# T11-MIDIThereminCPU.net
KiCad netlist of a schematic drawn in EAGLE
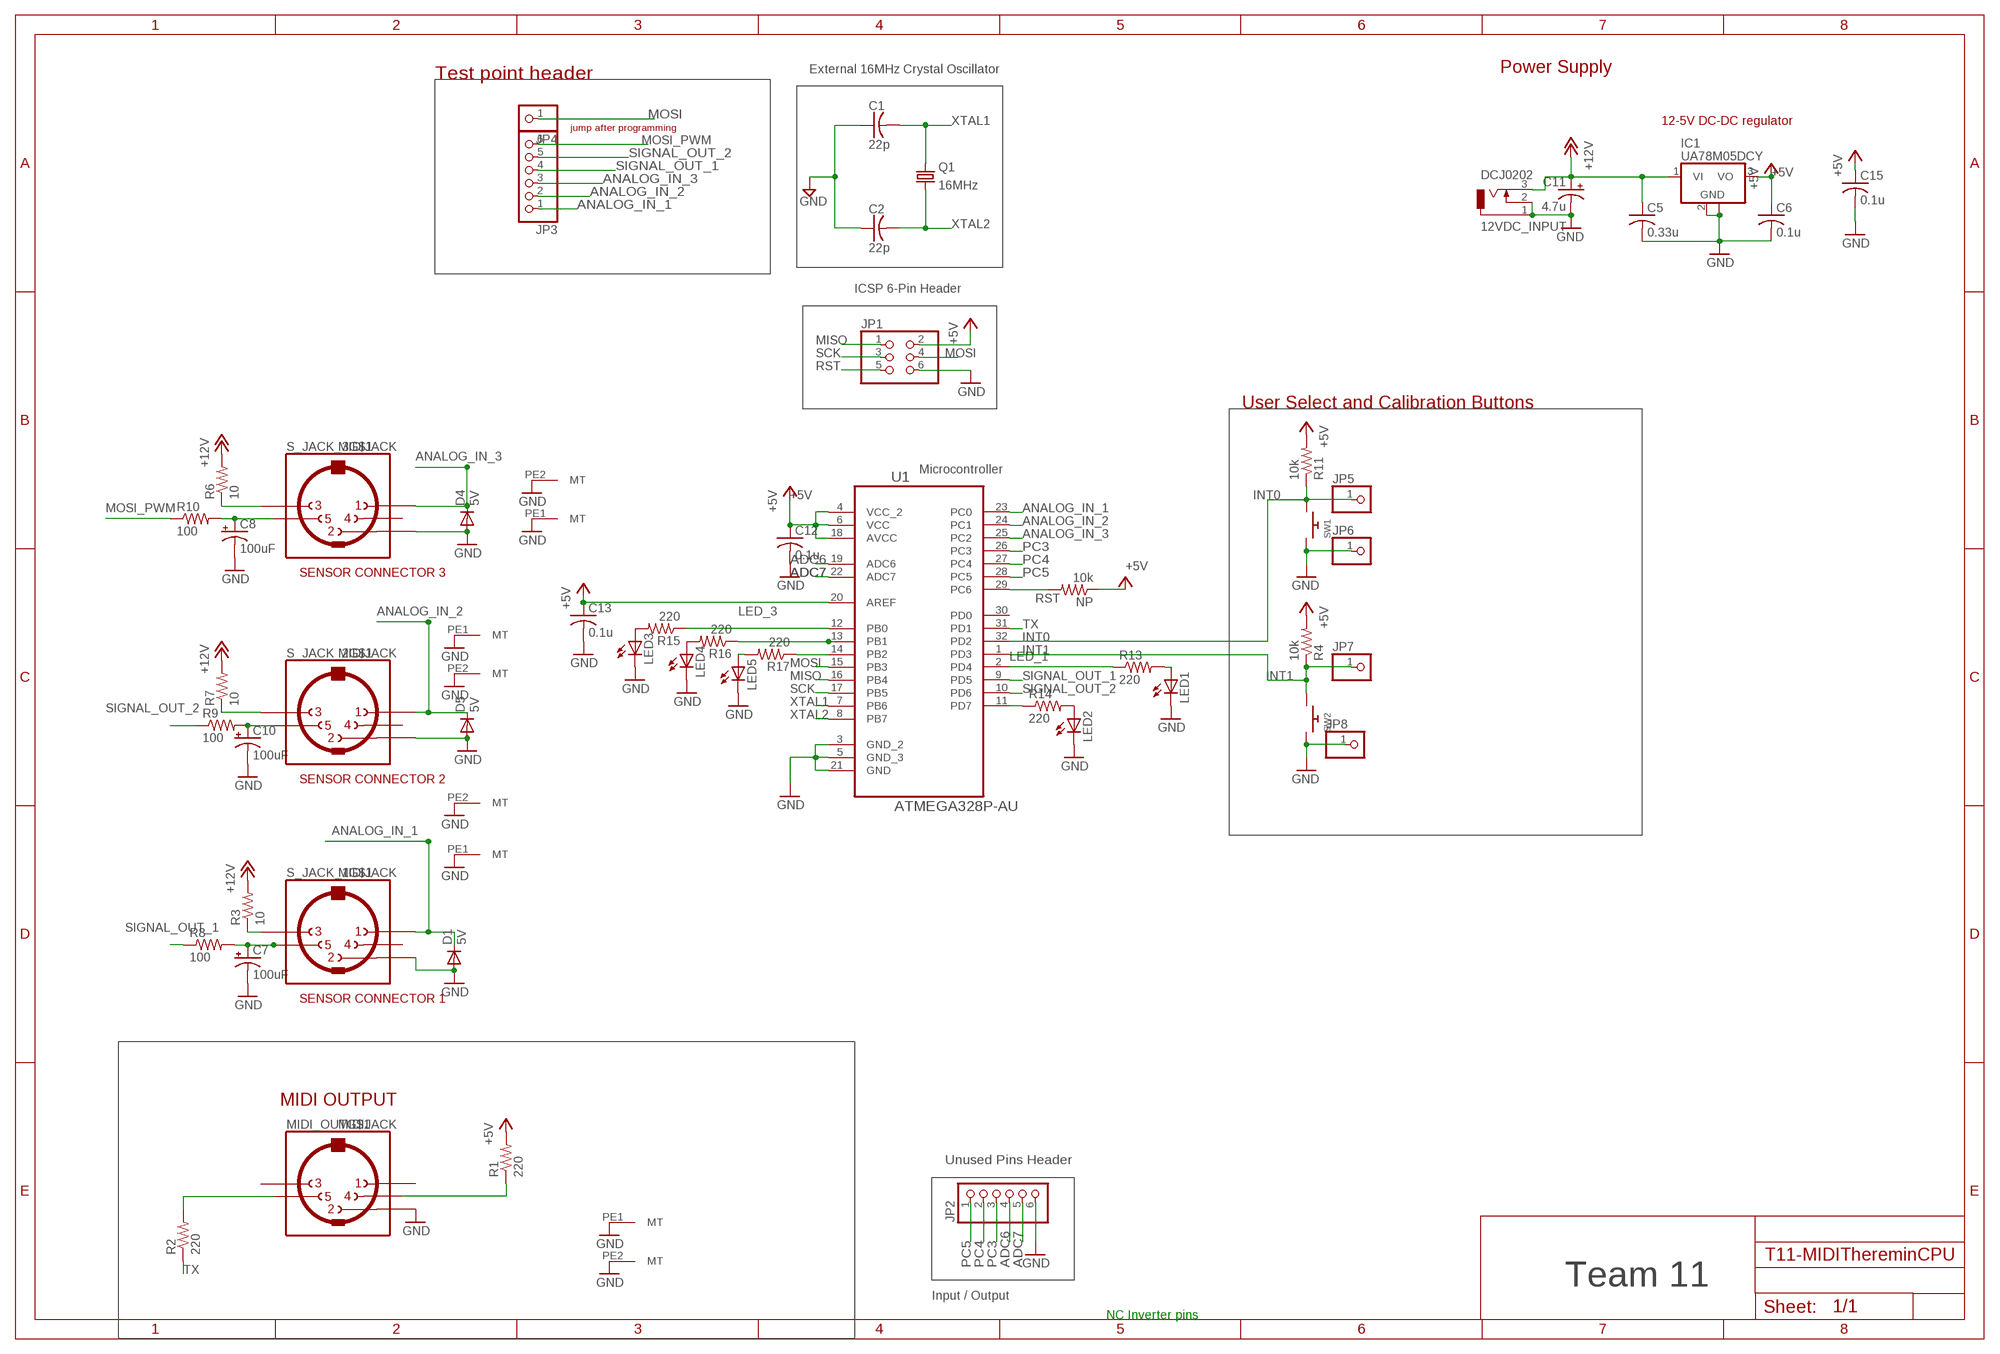
[diagram p0: schematic, sheet 1]

(export (version "E")
  (design (tool "Eeschema 10.0.6"))
  (components
    (comp (ref "12VDC_INPUT")
      (value "DCJ0202")
      (footprint "eagle-import:DCJ0202")
      (libsource (lib "eagle-import") (part "DCJ0202"))
    )
    (comp (ref "C1")
      (value "22p")
      (footprint "eagle-import:C0805")
      (libsource (lib "eagle-import") (part "C-USC0805"))
    )
    (comp (ref "C2")
      (value "22p")
      (footprint "eagle-import:C0805")
      (libsource (lib "eagle-import") (part "C-USC0805"))
    )
    (comp (ref "C5")
      (value "0.33u")
      (footprint "eagle-import:C0805")
      (libsource (lib "eagle-import") (part "C-USC0805"))
    )
    (comp (ref "C6")
      (value "0.1u")
      (footprint "eagle-import:C0805")
      (libsource (lib "eagle-import") (part "C-USC0805"))
    )
    (comp (ref "C7")
      (value "100uF")
      (footprint "eagle-import:E3,5-8")
      (libsource (lib "eagle-import") (part "CPOL-USE3.5-8"))
    )
    (comp (ref "C8")
      (value "100uF")
      (footprint "eagle-import:E3,5-8")
      (libsource (lib "eagle-import") (part "CPOL-USE3.5-8"))
    )
    (comp (ref "C10")
      (value "100uF")
      (footprint "eagle-import:E3,5-8")
      (libsource (lib "eagle-import") (part "CPOL-USE3.5-8"))
    )
    (comp (ref "C11")
      (value "4.7u")
      (footprint "eagle-import:E3,5-8")
      (libsource (lib "eagle-import") (part "CPOL-USE3.5-8"))
    )
    (comp (ref "C12")
      (value "0.1u")
      (footprint "eagle-import:C0805")
      (libsource (lib "eagle-import") (part "C-USC0805"))
    )
    (comp (ref "C13")
      (value "0.1u")
      (footprint "eagle-import:C0805")
      (libsource (lib "eagle-import") (part "C-USC0805"))
    )
    (comp (ref "C15")
      (value "0.1u")
      (footprint "eagle-import:C0805")
      (libsource (lib "eagle-import") (part "C-USC0805"))
    )
    (comp (ref "D1")
      (value "5V")
      (footprint "eagle-import:DO35-7")
      (libsource (lib "eagle-import") (part "1N4148DO35-7"))
    )
    (comp (ref "D4")
      (value "5V")
      (footprint "eagle-import:DO35-7")
      (libsource (lib "eagle-import") (part "1N4148DO35-7"))
    )
    (comp (ref "D5")
      (value "5V")
      (footprint "eagle-import:DO35-7")
      (libsource (lib "eagle-import") (part "1N4148DO35-7"))
    )
    (comp (ref "IC1")
      (value "UA78M05DCY")
      (footprint "eagle-import:SOT223")
      (libsource (lib "eagle-import") (part "UA78MDCY05"))
    )
    (comp (ref "JP1")
      (value "PINHD-2X3")
      (footprint "eagle-import:2X03")
      (libsource (lib "eagle-import") (part "PINHD-2X3"))
    )
    (comp (ref "JP2")
      (value "PINHD-1X6")
      (footprint "eagle-import:1X06")
      (libsource (lib "eagle-import") (part "PINHD-1X6"))
    )
    (comp (ref "JP3")
      (value "PINHD-1X6")
      (footprint "eagle-import:1X06")
      (libsource (lib "eagle-import") (part "PINHD-1X6"))
    )
    (comp (ref "JP4")
      (value "PINHD-1X1")
      (footprint "eagle-import:1X01")
      (libsource (lib "eagle-import") (part "PINHD-1X1"))
    )
    (comp (ref "JP5")
      (value "PINHD-1X1")
      (footprint "eagle-import:1X01")
      (libsource (lib "eagle-import") (part "PINHD-1X1"))
    )
    (comp (ref "JP6")
      (value "PINHD-1X1")
      (footprint "eagle-import:1X01")
      (libsource (lib "eagle-import") (part "PINHD-1X1"))
    )
    (comp (ref "JP7")
      (value "PINHD-1X1")
      (footprint "eagle-import:1X01")
      (libsource (lib "eagle-import") (part "PINHD-1X1"))
    )
    (comp (ref "JP8")
      (value "PINHD-1X1")
      (footprint "eagle-import:1X01")
      (libsource (lib "eagle-import") (part "PINHD-1X1"))
    )
    (comp (ref "LED1")
      (value "LED3MM")
      (footprint "eagle-import:LED3MM")
      (libsource (lib "eagle-import") (part "LED3MM"))
    )
    (comp (ref "LED2")
      (value "LED3MM")
      (footprint "eagle-import:LED3MM")
      (libsource (lib "eagle-import") (part "LED3MM"))
    )
    (comp (ref "LED3")
      (value "LED3MM")
      (footprint "eagle-import:LED3MM")
      (libsource (lib "eagle-import") (part "LED3MM"))
    )
    (comp (ref "LED4")
      (value "LED3MM")
      (footprint "eagle-import:LED3MM")
      (libsource (lib "eagle-import") (part "LED3MM"))
    )
    (comp (ref "LED5")
      (value "LED3MM")
      (footprint "eagle-import:LED3MM")
      (libsource (lib "eagle-import") (part "LED3MM"))
    )
    (comp (ref "MIDI_OUT")
      (value "MIDIJACK")
      (footprint "eagle-import:CP-2350")
      (libsource (lib "eagle-import") (part "MIDIJACK"))
    )
    (comp (ref "NP")
      (value "10k")
      (footprint "eagle-import:R0805")
      (libsource (lib "eagle-import") (part "R-US_R0805"))
    )
    (comp (ref "Q1")
      (value "16MHz")
      (footprint "eagle-import:SM49")
      (libsource (lib "eagle-import") (part "CRYSTALSM49"))
    )
    (comp (ref "R1")
      (value "220")
      (footprint "eagle-import:R0805")
      (libsource (lib "eagle-import") (part "R-US_R0805"))
    )
    (comp (ref "R2")
      (value "220")
      (footprint "eagle-import:M0805")
      (libsource (lib "eagle-import") (part "R-US_M0805"))
    )
    (comp (ref "R3")
      (value "10")
      (footprint "eagle-import:R0805")
      (libsource (lib "eagle-import") (part "R-US_R0805"))
    )
    (comp (ref "R4")
      (value "10k")
      (footprint "eagle-import:R0805")
      (libsource (lib "eagle-import") (part "R-US_R0805"))
    )
    (comp (ref "R6")
      (value "10")
      (footprint "eagle-import:M0805")
      (libsource (lib "eagle-import") (part "R-US_M0805"))
    )
    (comp (ref "R7")
      (value "10")
      (footprint "eagle-import:R0805")
      (libsource (lib "eagle-import") (part "R-US_R0805"))
    )
    (comp (ref "R8")
      (value "100")
      (footprint "eagle-import:R0805")
      (libsource (lib "eagle-import") (part "R-US_R0805"))
    )
    (comp (ref "R9")
      (value "100")
      (footprint "eagle-import:R0805")
      (libsource (lib "eagle-import") (part "R-US_R0805"))
    )
    (comp (ref "R10")
      (value "100")
      (footprint "eagle-import:M0805")
      (libsource (lib "eagle-import") (part "R-US_M0805"))
    )
    (comp (ref "R11")
      (value "10k")
      (footprint "eagle-import:R0805")
      (libsource (lib "eagle-import") (part "R-US_R0805"))
    )
    (comp (ref "R13")
      (value "220")
      (footprint "eagle-import:R0805")
      (libsource (lib "eagle-import") (part "R-US_R0805"))
    )
    (comp (ref "R14")
      (value "220")
      (footprint "eagle-import:R0805")
      (libsource (lib "eagle-import") (part "R-US_R0805"))
    )
    (comp (ref "R15")
      (value "220")
      (footprint "eagle-import:R0805")
      (libsource (lib "eagle-import") (part "R-US_R0805"))
    )
    (comp (ref "R16")
      (value "220")
      (footprint "eagle-import:R0805")
      (libsource (lib "eagle-import") (part "R-US_R0805"))
    )
    (comp (ref "R17")
      (value "220")
      (footprint "eagle-import:R0805")
      (libsource (lib "eagle-import") (part "R-US_R0805"))
    )
    (comp (ref "SW1")
      (value "SWITCH_PUSHBUTTONSOFTTOUCHSMD_SJ")
      (footprint "eagle-import:PUSHBUTTON_SMD_SJ")
      (libsource (lib "eagle-import") (part "SWITCH_PUSHBUTTONSOFTTOUCHSMD_SJ"))
    )
    (comp (ref "SW2")
      (value "SWITCH_PUSHBUTTONSOFTTOUCHSMD_SJ")
      (footprint "eagle-import:PUSHBUTTON_SMD_SJ")
      (libsource (lib "eagle-import") (part "SWITCH_PUSHBUTTONSOFTTOUCHSMD_SJ"))
    )
    (comp (ref "S_JACK_1")
      (value "MIDIJACK")
      (footprint "eagle-import:CP-2350")
      (libsource (lib "eagle-import") (part "MIDIJACK"))
    )
    (comp (ref "S_JACK_2")
      (value "MIDIJACK")
      (footprint "eagle-import:CP-2350")
      (libsource (lib "eagle-import") (part "MIDIJACK"))
    )
    (comp (ref "S_JACK_3")
      (value "MIDIJACK")
      (footprint "eagle-import:CP-2350")
      (libsource (lib "eagle-import") (part "MIDIJACK"))
    )
    (comp (ref "U1")
      (value "ATMEGA328P-AU")
      (footprint "eagle-import:QFP80P900X900X120-32N")
      (libsource (lib "eagle-import") (part "ATMEGA328P-AU"))
    )
  )
  (nets
    (net (code "1") (name "+5V") (class "Default")
      (node (ref "C12") (pin "1") (pinfunction "1_1") (pintype "passive"))
      (node (ref "C13") (pin "1") (pinfunction "1_1") (pintype "passive"))
      (node (ref "C15") (pin "1") (pinfunction "1_1") (pintype "passive"))
      (node (ref "C6") (pin "1") (pinfunction "1_1") (pintype "passive"))
      (node (ref "IC1") (pin "3") (pinfunction "VO_3") (pintype "passive"))
      (node (ref "JP1") (pin "2") (pinfunction "2_2") (pintype "passive"))
      (node (ref "NP") (pin "1") (pinfunction "1_1") (pintype "passive"))
      (node (ref "R1") (pin "2") (pinfunction "2_2") (pintype "passive"))
      (node (ref "R11") (pin "2") (pinfunction "2_2") (pintype "passive"))
      (node (ref "R4") (pin "2") (pinfunction "2_2") (pintype "passive"))
      (node (ref "U1") (pin "18") (pinfunction "AVCC_18") (pintype "power_in"))
      (node (ref "U1") (pin "20") (pinfunction "AREF_20") (pintype "input"))
      (node (ref "U1") (pin "4") (pinfunction "VCC_2_4") (pintype "power_in"))
      (node (ref "U1") (pin "6") (pinfunction "VCC_6") (pintype "power_in"))
    )
    (net (code "2") (name "+12V") (class "Default")
      (node (ref "12VDC_INPUT") (pin "3") (pinfunction "3_3") (pintype "passive"))
      (node (ref "C11") (pin "+") (pinfunction "+_+") (pintype "passive"))
      (node (ref "C5") (pin "1") (pinfunction "1_1") (pintype "passive"))
      (node (ref "IC1") (pin "1") (pinfunction "VI_1") (pintype "input"))
      (node (ref "R3") (pin "2") (pinfunction "2_2") (pintype "passive"))
      (node (ref "R6") (pin "2") (pinfunction "2_2") (pintype "passive"))
      (node (ref "R7") (pin "2") (pinfunction "2_2") (pintype "passive"))
    )
    (net (code "3") (name "/ADC6") (class "Default")
      (node (ref "JP2") (pin "4") (pinfunction "4_4") (pintype "passive"))
      (node (ref "U1") (pin "19") (pinfunction "ADC6_19") (pintype "input"))
    )
    (net (code "4") (name "/ADC7") (class "Default")
      (node (ref "JP2") (pin "5") (pinfunction "5_5") (pintype "passive"))
      (node (ref "U1") (pin "22") (pinfunction "ADC7_22") (pintype "input"))
    )
    (net (code "5") (name "/ANALOG_IN_1") (class "Default")
      (node (ref "D1") (pin "C") (pinfunction "C_C") (pintype "passive"))
      (node (ref "JP3") (pin "1") (pinfunction "1_1") (pintype "passive"))
      (node (ref "S_JACK_1") (pin "1") (pinfunction "1_1") (pintype "passive"))
      (node (ref "U1") (pin "23") (pinfunction "PC0_23") (pintype "bidirectional"))
    )
    (net (code "6") (name "/ANALOG_IN_2") (class "Default")
      (node (ref "D5") (pin "C") (pinfunction "C_C") (pintype "passive"))
      (node (ref "JP3") (pin "2") (pinfunction "2_2") (pintype "passive"))
      (node (ref "S_JACK_2") (pin "1") (pinfunction "1_1") (pintype "passive"))
      (node (ref "U1") (pin "24") (pinfunction "PC1_24") (pintype "bidirectional"))
    )
    (net (code "7") (name "/ANALOG_IN_3") (class "Default")
      (node (ref "D4") (pin "C") (pinfunction "C_C") (pintype "passive"))
      (node (ref "JP3") (pin "3") (pinfunction "3_3") (pintype "passive"))
      (node (ref "S_JACK_3") (pin "1") (pinfunction "1_1") (pintype "passive"))
      (node (ref "U1") (pin "25") (pinfunction "PC2_25") (pintype "bidirectional"))
    )
    (net (code "8") (name "/INT0") (class "Default")
      (node (ref "JP5") (pin "1") (pinfunction "1_1") (pintype "passive"))
      (node (ref "R11") (pin "1") (pinfunction "1_1") (pintype "passive"))
      (node (ref "SW1") (pin "P$2") (pinfunction "P$2_P$2") (pintype "passive"))
      (node (ref "U1") (pin "32") (pinfunction "PD2_32") (pintype "bidirectional"))
    )
    (net (code "9") (name "/INT1") (class "Default")
      (node (ref "JP7") (pin "1") (pinfunction "1_1") (pintype "passive"))
      (node (ref "R4") (pin "1") (pinfunction "1_1") (pintype "passive"))
      (node (ref "SW2") (pin "P$2") (pinfunction "P$2_P$2") (pintype "passive"))
      (node (ref "U1") (pin "1") (pinfunction "PD3_1") (pintype "bidirectional"))
    )
    (net (code "10") (name "/LED_1") (class "Default")
      (node (ref "R13") (pin "1") (pinfunction "1_1") (pintype "passive"))
      (node (ref "U1") (pin "2") (pinfunction "PD4_2") (pintype "bidirectional"))
    )
    (net (code "11") (name "/LED_3") (class "Default")
      (node (ref "R15") (pin "1") (pinfunction "1_1") (pintype "passive"))
      (node (ref "U1") (pin "12") (pinfunction "PB0_12") (pintype "bidirectional"))
    )
    (net (code "12") (name "/MISO") (class "Default")
      (node (ref "JP1") (pin "1") (pinfunction "1_1") (pintype "passive"))
      (node (ref "U1") (pin "16") (pinfunction "PB4_16") (pintype "bidirectional"))
    )
    (net (code "13") (name "/MOSI") (class "Default")
      (node (ref "JP1") (pin "4") (pinfunction "4_4") (pintype "passive"))
      (node (ref "JP4") (pin "1") (pinfunction "1_1") (pintype "passive"))
      (node (ref "U1") (pin "15") (pinfunction "PB3_15") (pintype "bidirectional"))
    )
    (net (code "14") (name "/MOSI_PWM") (class "Default")
      (node (ref "JP3") (pin "6") (pinfunction "6_6") (pintype "passive"))
      (node (ref "R10") (pin "1") (pinfunction "1_1") (pintype "passive"))
    )
    (net (code "15") (name "/PC3") (class "Default")
      (node (ref "JP2") (pin "3") (pinfunction "3_3") (pintype "passive"))
      (node (ref "U1") (pin "26") (pinfunction "PC3_26") (pintype "bidirectional"))
    )
    (net (code "16") (name "/PC4") (class "Default")
      (node (ref "JP2") (pin "2") (pinfunction "2_2") (pintype "passive"))
      (node (ref "U1") (pin "27") (pinfunction "PC4_27") (pintype "bidirectional"))
    )
    (net (code "17") (name "/PC5") (class "Default")
      (node (ref "JP2") (pin "1") (pinfunction "1_1") (pintype "passive"))
      (node (ref "U1") (pin "28") (pinfunction "PC5_28") (pintype "bidirectional"))
    )
    (net (code "18") (name "/RST") (class "Default")
      (node (ref "JP1") (pin "5") (pinfunction "5_5") (pintype "passive"))
      (node (ref "NP") (pin "2") (pinfunction "2_2") (pintype "passive"))
      (node (ref "U1") (pin "29") (pinfunction "PC6_29") (pintype "bidirectional"))
    )
    (net (code "19") (name "/SCK") (class "Default")
      (node (ref "JP1") (pin "3") (pinfunction "3_3") (pintype "passive"))
      (node (ref "U1") (pin "17") (pinfunction "PB5_17") (pintype "bidirectional"))
    )
    (net (code "20") (name "/SIGNAL_OUT_1") (class "Default")
      (node (ref "JP3") (pin "4") (pinfunction "4_4") (pintype "passive"))
      (node (ref "R8") (pin "1") (pinfunction "1_1") (pintype "passive"))
      (node (ref "U1") (pin "9") (pinfunction "PD5_9") (pintype "bidirectional"))
    )
    (net (code "21") (name "/SIGNAL_OUT_2") (class "Default")
      (node (ref "JP3") (pin "5") (pinfunction "5_5") (pintype "passive"))
      (node (ref "R9") (pin "1") (pinfunction "1_1") (pintype "passive"))
      (node (ref "U1") (pin "10") (pinfunction "PD6_10") (pintype "bidirectional"))
    )
    (net (code "22") (name "/TX") (class "Default")
      (node (ref "R2") (pin "1") (pinfunction "1_1") (pintype "passive"))
      (node (ref "U1") (pin "31") (pinfunction "PD1_31") (pintype "bidirectional"))
    )
    (net (code "23") (name "/XTAL1") (class "Default")
      (node (ref "C1") (pin "2") (pinfunction "2_2") (pintype "passive"))
      (node (ref "Q1") (pin "2") (pinfunction "2_2") (pintype "passive"))
      (node (ref "U1") (pin "7") (pinfunction "PB6_7") (pintype "bidirectional"))
    )
    (net (code "24") (name "/XTAL2") (class "Default")
      (node (ref "C2") (pin "2") (pinfunction "2_2") (pintype "passive"))
      (node (ref "Q1") (pin "1") (pinfunction "1_1") (pintype "passive"))
      (node (ref "U1") (pin "8") (pinfunction "PB7_8") (pintype "bidirectional"))
    )
    (net (code "25") (name "GND") (class "Default")
      (node (ref "12VDC_INPUT") (pin "1") (pinfunction "1_1") (pintype "passive"))
      (node (ref "12VDC_INPUT") (pin "2") (pinfunction "2_2") (pintype "passive"))
      (node (ref "C1") (pin "1") (pinfunction "1_1") (pintype "passive"))
      (node (ref "C10") (pin "-") (pinfunction "-_-") (pintype "passive"))
      (node (ref "C11") (pin "-") (pinfunction "-_-") (pintype "passive"))
      (node (ref "C12") (pin "2") (pinfunction "2_2") (pintype "passive"))
      (node (ref "C13") (pin "2") (pinfunction "2_2") (pintype "passive"))
      (node (ref "C15") (pin "2") (pinfunction "2_2") (pintype "passive"))
      (node (ref "C2") (pin "1") (pinfunction "1_1") (pintype "passive"))
      (node (ref "C5") (pin "2") (pinfunction "2_2") (pintype "passive"))
      (node (ref "C6") (pin "2") (pinfunction "2_2") (pintype "passive"))
      (node (ref "C7") (pin "-") (pinfunction "-_-") (pintype "passive"))
      (node (ref "C8") (pin "-") (pinfunction "-_-") (pintype "passive"))
      (node (ref "D1") (pin "A") (pinfunction "A_A") (pintype "passive"))
      (node (ref "D4") (pin "A") (pinfunction "A_A") (pintype "passive"))
      (node (ref "D5") (pin "A") (pinfunction "A_A") (pintype "passive"))
      (node (ref "IC1") (pin "2") (pinfunction "GND_2") (pintype "passive"))
      (node (ref "IC1") (pin "4") (pinfunction "GND_4") (pintype "passive"))
      (node (ref "JP1") (pin "6") (pinfunction "6_6") (pintype "passive"))
      (node (ref "JP2") (pin "6") (pinfunction "6_6") (pintype "passive"))
      (node (ref "JP6") (pin "1") (pinfunction "1_1") (pintype "passive"))
      (node (ref "JP8") (pin "1") (pinfunction "1_1") (pintype "passive"))
      (node (ref "LED1") (pin "K") (pinfunction "C_K") (pintype "passive"))
      (node (ref "LED2") (pin "K") (pinfunction "C_K") (pintype "passive"))
      (node (ref "LED3") (pin "K") (pinfunction "C_K") (pintype "passive"))
      (node (ref "LED4") (pin "K") (pinfunction "C_K") (pintype "passive"))
      (node (ref "LED5") (pin "K") (pinfunction "C_K") (pintype "passive"))
      (node (ref "MIDI_OUT") (pin "2") (pinfunction "2_2") (pintype "passive"))
      (node (ref "MIDI_OUT") (pin "PE1") (pinfunction "MT_PE1") (pintype "passive"))
      (node (ref "MIDI_OUT") (pin "PE2") (pinfunction "MT_PE2") (pintype "passive"))
      (node (ref "SW1") (pin "P$1") (pinfunction "P$1_P$1") (pintype "passive"))
      (node (ref "SW2") (pin "P$1") (pinfunction "P$1_P$1") (pintype "passive"))
      (node (ref "S_JACK_1") (pin "2") (pinfunction "2_2") (pintype "passive"))
      (node (ref "S_JACK_1") (pin "PE1") (pinfunction "MT_PE1") (pintype "passive"))
      (node (ref "S_JACK_1") (pin "PE2") (pinfunction "MT_PE2") (pintype "passive"))
      (node (ref "S_JACK_2") (pin "2") (pinfunction "2_2") (pintype "passive"))
      (node (ref "S_JACK_2") (pin "PE1") (pinfunction "MT_PE1") (pintype "passive"))
      (node (ref "S_JACK_2") (pin "PE2") (pinfunction "MT_PE2") (pintype "passive"))
      (node (ref "S_JACK_3") (pin "2") (pinfunction "2_2") (pintype "passive"))
      (node (ref "S_JACK_3") (pin "PE1") (pinfunction "MT_PE1") (pintype "passive"))
      (node (ref "S_JACK_3") (pin "PE2") (pinfunction "MT_PE2") (pintype "passive"))
      (node (ref "U1") (pin "21") (pinfunction "GND_21") (pintype "passive"))
      (node (ref "U1") (pin "3") (pinfunction "GND_2_3") (pintype "passive"))
      (node (ref "U1") (pin "5") (pinfunction "GND_3_5") (pintype "passive"))
    )
    (net (code "26") (name "Net-(C7-Pad+)") (class "Default")
      (node (ref "C7") (pin "+") (pinfunction "+_+") (pintype "passive"))
      (node (ref "R8") (pin "2") (pinfunction "2_2") (pintype "passive"))
      (node (ref "S_JACK_1") (pin "5") (pinfunction "5_5") (pintype "passive"))
    )
    (net (code "27") (name "Net-(C8-Pad+)") (class "Default")
      (node (ref "C8") (pin "+") (pinfunction "+_+") (pintype "passive"))
      (node (ref "R10") (pin "2") (pinfunction "2_2") (pintype "passive"))
      (node (ref "S_JACK_3") (pin "5") (pinfunction "5_5") (pintype "passive"))
    )
    (net (code "28") (name "Net-(C10-Pad+)") (class "Default")
      (node (ref "C10") (pin "+") (pinfunction "+_+") (pintype "passive"))
      (node (ref "R9") (pin "2") (pinfunction "2_2") (pintype "passive"))
      (node (ref "S_JACK_2") (pin "5") (pinfunction "5_5") (pintype "passive"))
    )
    (net (code "29") (name "Net-(LED1-PadA)") (class "Default")
      (node (ref "LED1") (pin "A") (pinfunction "A_A") (pintype "passive"))
      (node (ref "R13") (pin "2") (pinfunction "2_2") (pintype "passive"))
    )
    (net (code "30") (name "Net-(LED2-PadA)") (class "Default")
      (node (ref "LED2") (pin "A") (pinfunction "A_A") (pintype "passive"))
      (node (ref "R14") (pin "2") (pinfunction "2_2") (pintype "passive"))
    )
    (net (code "31") (name "Net-(LED3-PadA)") (class "Default")
      (node (ref "LED3") (pin "A") (pinfunction "A_A") (pintype "passive"))
      (node (ref "R15") (pin "2") (pinfunction "2_2") (pintype "passive"))
    )
    (net (code "32") (name "Net-(LED4-PadA)") (class "Default")
      (node (ref "LED4") (pin "A") (pinfunction "A_A") (pintype "passive"))
      (node (ref "R16") (pin "2") (pinfunction "2_2") (pintype "passive"))
    )
    (net (code "33") (name "Net-(LED5-PadA)") (class "Default")
      (node (ref "LED5") (pin "A") (pinfunction "A_A") (pintype "passive"))
      (node (ref "R17") (pin "2") (pinfunction "2_2") (pintype "passive"))
    )
    (net (code "34") (name "Net-(MIDI_OUT-Pad4)") (class "Default")
      (node (ref "MIDI_OUT") (pin "4") (pinfunction "4_4") (pintype "passive"))
      (node (ref "R1") (pin "1") (pinfunction "1_1") (pintype "passive"))
    )
    (net (code "35") (name "Net-(MIDI_OUT-Pad5)") (class "Default")
      (node (ref "MIDI_OUT") (pin "5") (pinfunction "5_5") (pintype "passive"))
      (node (ref "R2") (pin "2") (pinfunction "2_2") (pintype "passive"))
    )
    (net (code "36") (name "Net-(R3-Pad1)") (class "Default")
      (node (ref "R3") (pin "1") (pinfunction "1_1") (pintype "passive"))
      (node (ref "S_JACK_1") (pin "3") (pinfunction "3_3") (pintype "passive"))
    )
    (net (code "37") (name "Net-(R6-Pad1)") (class "Default")
      (node (ref "R6") (pin "1") (pinfunction "1_1") (pintype "passive"))
      (node (ref "S_JACK_3") (pin "3") (pinfunction "3_3") (pintype "passive"))
    )
    (net (code "38") (name "Net-(R7-Pad1)") (class "Default")
      (node (ref "R7") (pin "1") (pinfunction "1_1") (pintype "passive"))
      (node (ref "S_JACK_2") (pin "3") (pinfunction "3_3") (pintype "passive"))
    )
    (net (code "39") (name "Net-(U1-PB1)") (class "Default")
      (node (ref "R16") (pin "1") (pinfunction "1_1") (pintype "passive"))
      (node (ref "U1") (pin "13") (pinfunction "PB1_13") (pintype "bidirectional"))
    )
    (net (code "40") (name "Net-(U1-PB2)") (class "Default")
      (node (ref "R17") (pin "1") (pinfunction "1_1") (pintype "passive"))
      (node (ref "U1") (pin "14") (pinfunction "PB2_14") (pintype "bidirectional"))
    )
    (net (code "41") (name "Net-(U1-PD7)") (class "Default")
      (node (ref "R14") (pin "1") (pinfunction "1_1") (pintype "passive"))
      (node (ref "U1") (pin "11") (pinfunction "PD7_11") (pintype "bidirectional"))
    )
    (net (code "42") (name "unconnected-(MIDI_OUT-Pad1)") (class "Default")
      (node (ref "MIDI_OUT") (pin "1") (pinfunction "1_1") (pintype "passive"))
    )
    (net (code "43") (name "unconnected-(MIDI_OUT-Pad3)") (class "Default")
      (node (ref "MIDI_OUT") (pin "3") (pinfunction "3_3") (pintype "passive"))
    )
    (net (code "44") (name "unconnected-(S_JACK_1-Pad4)") (class "Default")
      (node (ref "S_JACK_1") (pin "4") (pinfunction "4_4") (pintype "passive"))
    )
    (net (code "45") (name "unconnected-(S_JACK_2-Pad4)") (class "Default")
      (node (ref "S_JACK_2") (pin "4") (pinfunction "4_4") (pintype "passive"))
    )
    (net (code "46") (name "unconnected-(S_JACK_3-Pad4)") (class "Default")
      (node (ref "S_JACK_3") (pin "4") (pinfunction "4_4") (pintype "passive"))
    )
    (net (code "47") (name "unconnected-(U1-PD0-Pad30)") (class "Default")
      (node (ref "U1") (pin "30") (pinfunction "PD0_30") (pintype "bidirectional"))
    )
  )
)
